# MultiSensor_MPL_PCA_0805.net
KiCad netlist of a schematic drawn in EAGLE
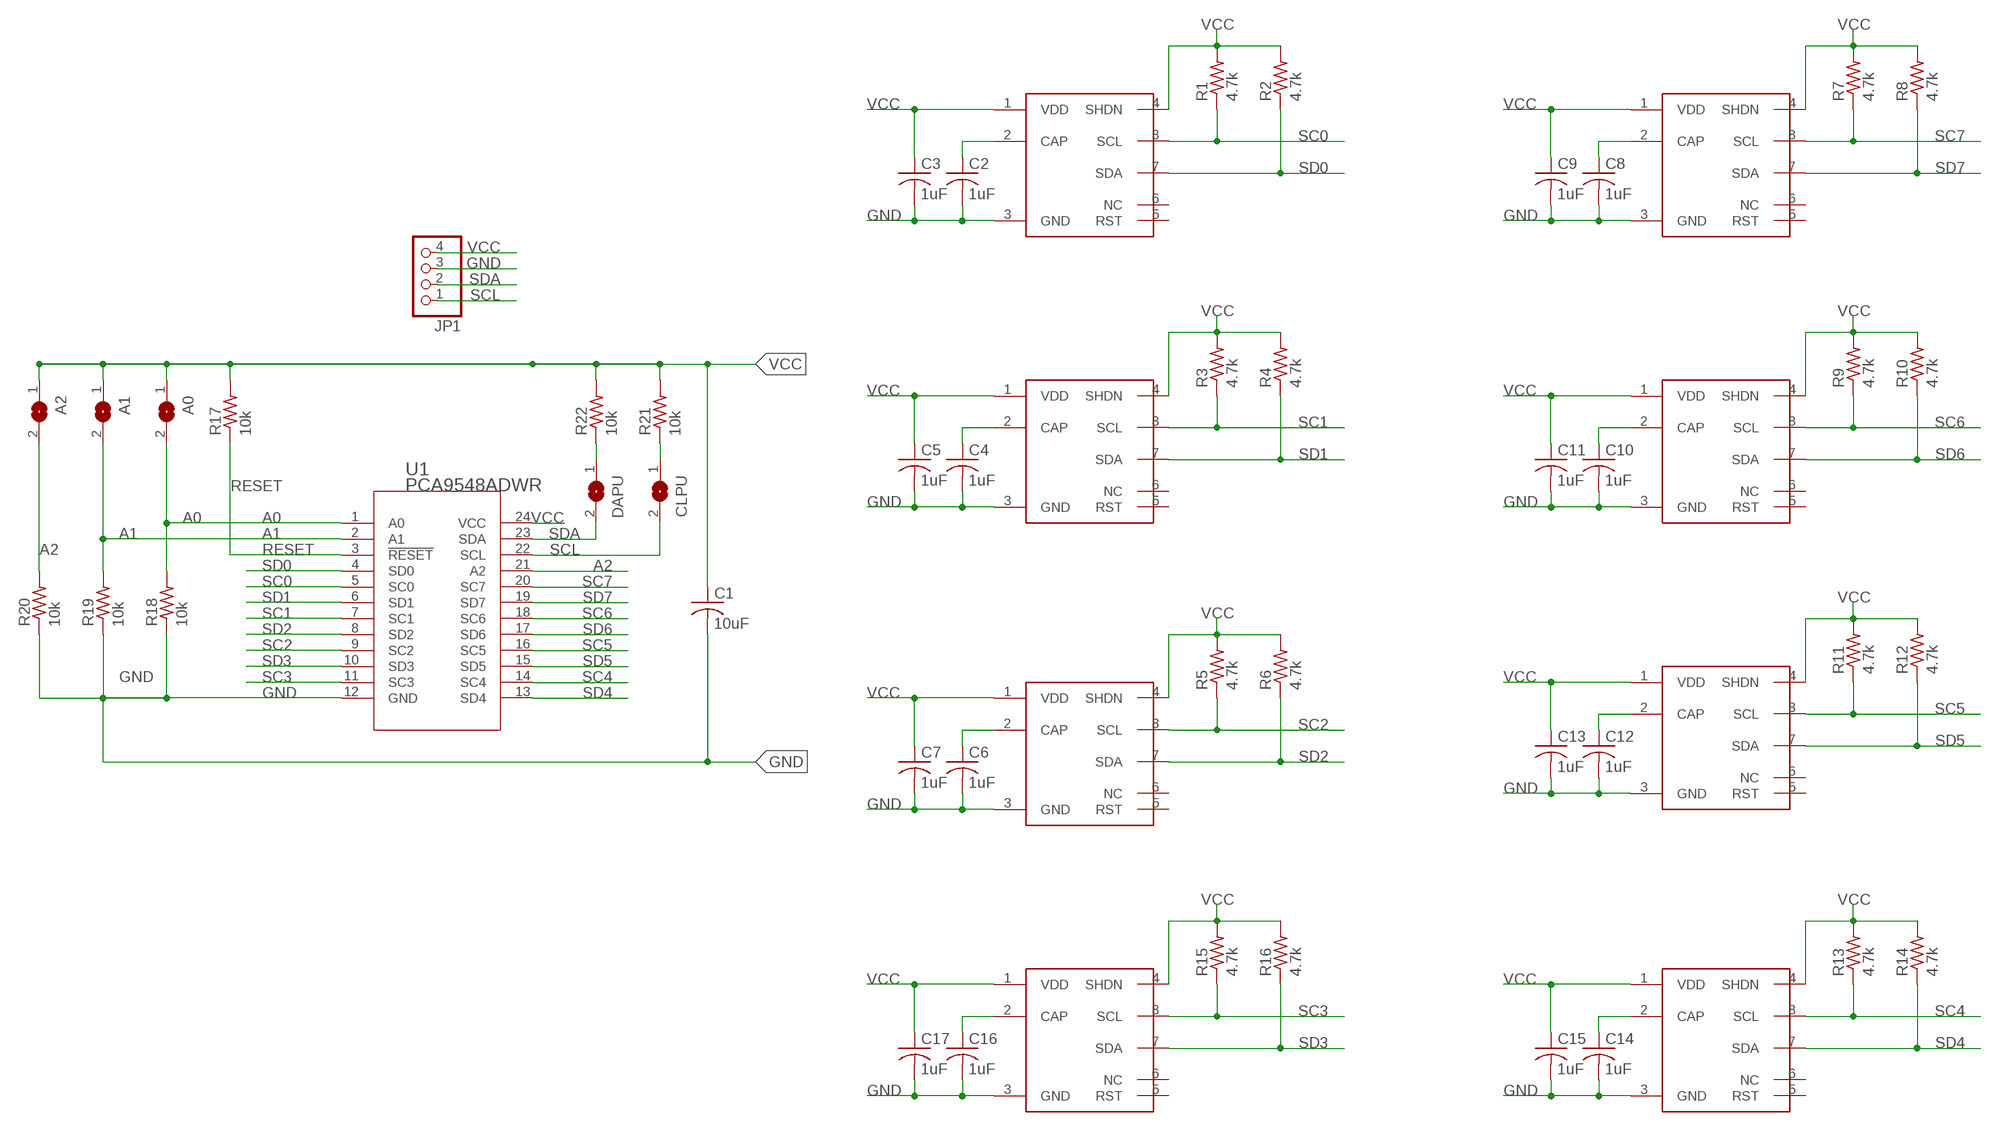
[diagram p0: schematic, sheet 1]

(export (version "E")
  (design (tool "Eeschema 10.0.6"))
  (components
    (comp (ref "A0") (value "SJ") (footprint "eagle-import:SJ") (libsource (lib "eagle-import") (part "SJ")))
    (comp (ref "A1") (value "SJ") (footprint "eagle-import:SJ") (libsource (lib "eagle-import") (part "SJ")))
    (comp (ref "A2") (value "SJ") (footprint "eagle-import:SJ") (libsource (lib "eagle-import") (part "SJ")))
    (comp (ref "B1")
      (value "MPL115A2T1")
      (footprint "eagle-import:MPL115A2T1")
      (libsource (lib "eagle-import") (part "MPL115A2T1"))
    )
    (comp (ref "B2")
      (value "MPL115A2T1")
      (footprint "eagle-import:MPL115A2T1")
      (libsource (lib "eagle-import") (part "MPL115A2T1"))
    )
    (comp (ref "B3")
      (value "MPL115A2T1")
      (footprint "eagle-import:MPL115A2T1")
      (libsource (lib "eagle-import") (part "MPL115A2T1"))
    )
    (comp (ref "B4")
      (value "MPL115A2T1")
      (footprint "eagle-import:MPL115A2T1")
      (libsource (lib "eagle-import") (part "MPL115A2T1"))
    )
    (comp (ref "B5")
      (value "MPL115A2T1")
      (footprint "eagle-import:MPL115A2T1")
      (libsource (lib "eagle-import") (part "MPL115A2T1"))
    )
    (comp (ref "B6")
      (value "MPL115A2T1")
      (footprint "eagle-import:MPL115A2T1")
      (libsource (lib "eagle-import") (part "MPL115A2T1"))
    )
    (comp (ref "B7")
      (value "MPL115A2T1")
      (footprint "eagle-import:MPL115A2T1")
      (libsource (lib "eagle-import") (part "MPL115A2T1"))
    )
    (comp (ref "B8")
      (value "MPL115A2T1")
      (footprint "eagle-import:MPL115A2T1")
      (libsource (lib "eagle-import") (part "MPL115A2T1"))
    )
    (comp (ref "C1")
      (value "10uF")
      (footprint "eagle-import:C1206")
      (libsource (lib "eagle-import") (part "C-USC1206"))
    )
    (comp (ref "C2")
      (value "1uF")
      (footprint "eagle-import:C0805")
      (libsource (lib "eagle-import") (part "C-USC0805"))
    )
    (comp (ref "C3")
      (value "1uF")
      (footprint "eagle-import:C0805")
      (libsource (lib "eagle-import") (part "C-USC0805"))
    )
    (comp (ref "C4")
      (value "1uF")
      (footprint "eagle-import:C0805")
      (libsource (lib "eagle-import") (part "C-USC0805"))
    )
    (comp (ref "C5")
      (value "1uF")
      (footprint "eagle-import:C0805")
      (libsource (lib "eagle-import") (part "C-USC0805"))
    )
    (comp (ref "C6")
      (value "1uF")
      (footprint "eagle-import:C0805")
      (libsource (lib "eagle-import") (part "C-USC0805"))
    )
    (comp (ref "C7")
      (value "1uF")
      (footprint "eagle-import:C0805")
      (libsource (lib "eagle-import") (part "C-USC0805"))
    )
    (comp (ref "C8")
      (value "1uF")
      (footprint "eagle-import:C0805")
      (libsource (lib "eagle-import") (part "C-USC0805"))
    )
    (comp (ref "C9")
      (value "1uF")
      (footprint "eagle-import:C0805")
      (libsource (lib "eagle-import") (part "C-USC0805"))
    )
    (comp (ref "C10")
      (value "1uF")
      (footprint "eagle-import:C0805")
      (libsource (lib "eagle-import") (part "C-USC0805"))
    )
    (comp (ref "C11")
      (value "1uF")
      (footprint "eagle-import:C0805")
      (libsource (lib "eagle-import") (part "C-USC0805"))
    )
    (comp (ref "C12")
      (value "1uF")
      (footprint "eagle-import:C0805")
      (libsource (lib "eagle-import") (part "C-USC0805"))
    )
    (comp (ref "C13")
      (value "1uF")
      (footprint "eagle-import:C0805")
      (libsource (lib "eagle-import") (part "C-USC0805"))
    )
    (comp (ref "C14")
      (value "1uF")
      (footprint "eagle-import:C0805")
      (libsource (lib "eagle-import") (part "C-USC0805"))
    )
    (comp (ref "C15")
      (value "1uF")
      (footprint "eagle-import:C0805")
      (libsource (lib "eagle-import") (part "C-USC0805"))
    )
    (comp (ref "C16")
      (value "1uF")
      (footprint "eagle-import:C0805")
      (libsource (lib "eagle-import") (part "C-USC0805"))
    )
    (comp (ref "C17")
      (value "1uF")
      (footprint "eagle-import:C0805")
      (libsource (lib "eagle-import") (part "C-USC0805"))
    )
    (comp (ref "CLPU")
      (value "SJ")
      (footprint "eagle-import:SJ")
      (libsource (lib "eagle-import") (part "SJ"))
    )
    (comp (ref "DAPU")
      (value "SJ")
      (footprint "eagle-import:SJ")
      (libsource (lib "eagle-import") (part "SJ"))
    )
    (comp (ref "JP1")
      (value "PINHD-1X4")
      (footprint "eagle-import:1X04")
      (libsource (lib "eagle-import") (part "PINHD-1X4"))
    )
    (comp (ref "R1")
      (value "4.7k")
      (footprint "eagle-import:R0805")
      (libsource (lib "eagle-import") (part "R-US_R0805"))
    )
    (comp (ref "R2")
      (value "4.7k")
      (footprint "eagle-import:R0805")
      (libsource (lib "eagle-import") (part "R-US_R0805"))
    )
    (comp (ref "R3")
      (value "4.7k")
      (footprint "eagle-import:R0805")
      (libsource (lib "eagle-import") (part "R-US_R0805"))
    )
    (comp (ref "R4")
      (value "4.7k")
      (footprint "eagle-import:R0805")
      (libsource (lib "eagle-import") (part "R-US_R0805"))
    )
    (comp (ref "R5")
      (value "4.7k")
      (footprint "eagle-import:R0805")
      (libsource (lib "eagle-import") (part "R-US_R0805"))
    )
    (comp (ref "R6")
      (value "4.7k")
      (footprint "eagle-import:R0805")
      (libsource (lib "eagle-import") (part "R-US_R0805"))
    )
    (comp (ref "R7")
      (value "4.7k")
      (footprint "eagle-import:R0805")
      (libsource (lib "eagle-import") (part "R-US_R0805"))
    )
    (comp (ref "R8")
      (value "4.7k")
      (footprint "eagle-import:R0805")
      (libsource (lib "eagle-import") (part "R-US_R0805"))
    )
    (comp (ref "R9")
      (value "4.7k")
      (footprint "eagle-import:R0805")
      (libsource (lib "eagle-import") (part "R-US_R0805"))
    )
    (comp (ref "R10")
      (value "4.7k")
      (footprint "eagle-import:R0805")
      (libsource (lib "eagle-import") (part "R-US_R0805"))
    )
    (comp (ref "R11")
      (value "4.7k")
      (footprint "eagle-import:R0805")
      (libsource (lib "eagle-import") (part "R-US_R0805"))
    )
    (comp (ref "R12")
      (value "4.7k")
      (footprint "eagle-import:R0805")
      (libsource (lib "eagle-import") (part "R-US_R0805"))
    )
    (comp (ref "R13")
      (value "4.7k")
      (footprint "eagle-import:R0805")
      (libsource (lib "eagle-import") (part "R-US_R0805"))
    )
    (comp (ref "R14")
      (value "4.7k")
      (footprint "eagle-import:R0805")
      (libsource (lib "eagle-import") (part "R-US_R0805"))
    )
    (comp (ref "R15")
      (value "4.7k")
      (footprint "eagle-import:R0805")
      (libsource (lib "eagle-import") (part "R-US_R0805"))
    )
    (comp (ref "R16")
      (value "4.7k")
      (footprint "eagle-import:R0805")
      (libsource (lib "eagle-import") (part "R-US_R0805"))
    )
    (comp (ref "R17")
      (value "10k")
      (footprint "eagle-import:R0805")
      (libsource (lib "eagle-import") (part "resistor_348_R-US_R0805"))
    )
    (comp (ref "R18")
      (value "10k")
      (footprint "eagle-import:R0805")
      (libsource (lib "eagle-import") (part "resistor_348_R-US_R0805"))
    )
    (comp (ref "R19")
      (value "10k")
      (footprint "eagle-import:R0805")
      (libsource (lib "eagle-import") (part "resistor_348_R-US_R0805"))
    )
    (comp (ref "R20")
      (value "10k")
      (footprint "eagle-import:R0805")
      (libsource (lib "eagle-import") (part "resistor_348_R-US_R0805"))
    )
    (comp (ref "R21")
      (value "10k")
      (footprint "eagle-import:R0805")
      (libsource (lib "eagle-import") (part "resistor_348_R-US_R0805"))
    )
    (comp (ref "R22")
      (value "10k")
      (footprint "eagle-import:R0805")
      (libsource (lib "eagle-import") (part "resistor_348_R-US_R0805"))
    )
    (comp (ref "U1")
      (value "PCA9548ADWR")
      (footprint "eagle-import:DW24")
      (fields
        (field (name "GENERIC_PART_NUMBER") "PCA9548A")
        (field (name "MANUFACTURER") "Texas Instruments")
      )
      (libsource (lib "eagle-import") (part "PCA9548ADWR"))
    )
  )
  (nets
    (net (code "1") (name "/A0") (class "Default")
      (node (ref "A0") (pin "2") (pinfunction "2_2") (pintype "passive"))
      (node (ref "R18") (pin "2") (pinfunction "2_2") (pintype "passive"))
      (node (ref "U1") (pin "1") (pinfunction "A0_1") (pintype "input"))
    )
    (net (code "2") (name "/A1") (class "Default")
      (node (ref "A1") (pin "2") (pinfunction "2_2") (pintype "passive"))
      (node (ref "R19") (pin "2") (pinfunction "2_2") (pintype "passive"))
      (node (ref "U1") (pin "2") (pinfunction "A1_2") (pintype "input"))
    )
    (net (code "3") (name "/A2") (class "Default")
      (node (ref "A2") (pin "2") (pinfunction "2_2") (pintype "passive"))
      (node (ref "R20") (pin "2") (pinfunction "2_2") (pintype "passive"))
      (node (ref "U1") (pin "21") (pinfunction "A2_21") (pintype "input"))
    )
    (net (code "4") (name "/RESET") (class "Default")
      (node (ref "R17") (pin "1") (pinfunction "1_1") (pintype "passive"))
      (node (ref "U1") (pin "3") (pinfunction "~{RESET}_3") (pintype "input"))
    )
    (net (code "5") (name "/SC0") (class "Default")
      (node (ref "B1") (pin "8") (pinfunction "SCL_8") (pintype "bidirectional"))
      (node (ref "R1") (pin "1") (pinfunction "1_1") (pintype "passive"))
      (node (ref "U1") (pin "5") (pinfunction "SC0_5") (pintype "passive"))
    )
    (net (code "6") (name "/SC1") (class "Default")
      (node (ref "B2") (pin "8") (pinfunction "SCL_8") (pintype "bidirectional"))
      (node (ref "R3") (pin "1") (pinfunction "1_1") (pintype "passive"))
      (node (ref "U1") (pin "7") (pinfunction "SC1_7") (pintype "passive"))
    )
    (net (code "7") (name "/SC2") (class "Default")
      (node (ref "B3") (pin "8") (pinfunction "SCL_8") (pintype "bidirectional"))
      (node (ref "R5") (pin "1") (pinfunction "1_1") (pintype "passive"))
      (node (ref "U1") (pin "9") (pinfunction "SC2_9") (pintype "passive"))
    )
    (net (code "8") (name "/SC3") (class "Default")
      (node (ref "B8") (pin "8") (pinfunction "SCL_8") (pintype "bidirectional"))
      (node (ref "R15") (pin "1") (pinfunction "1_1") (pintype "passive"))
      (node (ref "U1") (pin "11") (pinfunction "SC3_11") (pintype "passive"))
    )
    (net (code "9") (name "/SC4") (class "Default")
      (node (ref "B7") (pin "8") (pinfunction "SCL_8") (pintype "bidirectional"))
      (node (ref "R13") (pin "1") (pinfunction "1_1") (pintype "passive"))
      (node (ref "U1") (pin "14") (pinfunction "SC4_14") (pintype "passive"))
    )
    (net (code "10") (name "/SC5") (class "Default")
      (node (ref "B6") (pin "8") (pinfunction "SCL_8") (pintype "bidirectional"))
      (node (ref "R11") (pin "1") (pinfunction "1_1") (pintype "passive"))
      (node (ref "U1") (pin "16") (pinfunction "SC5_16") (pintype "passive"))
    )
    (net (code "11") (name "/SC6") (class "Default")
      (node (ref "B5") (pin "8") (pinfunction "SCL_8") (pintype "bidirectional"))
      (node (ref "R9") (pin "1") (pinfunction "1_1") (pintype "passive"))
      (node (ref "U1") (pin "18") (pinfunction "SC6_18") (pintype "passive"))
    )
    (net (code "12") (name "/SC7") (class "Default")
      (node (ref "B4") (pin "8") (pinfunction "SCL_8") (pintype "bidirectional"))
      (node (ref "R7") (pin "1") (pinfunction "1_1") (pintype "passive"))
      (node (ref "U1") (pin "20") (pinfunction "SC7_20") (pintype "passive"))
    )
    (net (code "13") (name "/SCL") (class "Default")
      (node (ref "CLPU") (pin "2") (pinfunction "2_2") (pintype "passive"))
      (node (ref "JP1") (pin "1") (pinfunction "1_1") (pintype "passive"))
      (node (ref "U1") (pin "22") (pinfunction "SCL_22") (pintype "passive"))
    )
    (net (code "14") (name "/SD0") (class "Default")
      (node (ref "B1") (pin "7") (pinfunction "SDA_7") (pintype "bidirectional"))
      (node (ref "R2") (pin "1") (pinfunction "1_1") (pintype "passive"))
      (node (ref "U1") (pin "4") (pinfunction "SD0_4") (pintype "passive"))
    )
    (net (code "15") (name "/SD1") (class "Default")
      (node (ref "B2") (pin "7") (pinfunction "SDA_7") (pintype "bidirectional"))
      (node (ref "R4") (pin "1") (pinfunction "1_1") (pintype "passive"))
      (node (ref "U1") (pin "6") (pinfunction "SD1_6") (pintype "passive"))
    )
    (net (code "16") (name "/SD2") (class "Default")
      (node (ref "B3") (pin "7") (pinfunction "SDA_7") (pintype "bidirectional"))
      (node (ref "R6") (pin "1") (pinfunction "1_1") (pintype "passive"))
      (node (ref "U1") (pin "8") (pinfunction "SD2_8") (pintype "passive"))
    )
    (net (code "17") (name "/SD3") (class "Default")
      (node (ref "B8") (pin "7") (pinfunction "SDA_7") (pintype "bidirectional"))
      (node (ref "R16") (pin "1") (pinfunction "1_1") (pintype "passive"))
      (node (ref "U1") (pin "10") (pinfunction "SD3_10") (pintype "passive"))
    )
    (net (code "18") (name "/SD4") (class "Default")
      (node (ref "B7") (pin "7") (pinfunction "SDA_7") (pintype "bidirectional"))
      (node (ref "R14") (pin "1") (pinfunction "1_1") (pintype "passive"))
      (node (ref "U1") (pin "13") (pinfunction "SD4_13") (pintype "passive"))
    )
    (net (code "19") (name "/SD5") (class "Default")
      (node (ref "B6") (pin "7") (pinfunction "SDA_7") (pintype "bidirectional"))
      (node (ref "R12") (pin "1") (pinfunction "1_1") (pintype "passive"))
      (node (ref "U1") (pin "15") (pinfunction "SD5_15") (pintype "passive"))
    )
    (net (code "20") (name "/SD6") (class "Default")
      (node (ref "B5") (pin "7") (pinfunction "SDA_7") (pintype "bidirectional"))
      (node (ref "R10") (pin "1") (pinfunction "1_1") (pintype "passive"))
      (node (ref "U1") (pin "17") (pinfunction "SD6_17") (pintype "passive"))
    )
    (net (code "21") (name "/SD7") (class "Default")
      (node (ref "B4") (pin "7") (pinfunction "SDA_7") (pintype "bidirectional"))
      (node (ref "R8") (pin "1") (pinfunction "1_1") (pintype "passive"))
      (node (ref "U1") (pin "19") (pinfunction "SD7_19") (pintype "passive"))
    )
    (net (code "22") (name "/SDA") (class "Default")
      (node (ref "DAPU") (pin "2") (pinfunction "2_2") (pintype "passive"))
      (node (ref "JP1") (pin "2") (pinfunction "2_2") (pintype "passive"))
      (node (ref "U1") (pin "23") (pinfunction "SDA_23") (pintype "passive"))
    )
    (net (code "23") (name "GND") (class "Default")
      (node (ref "B1") (pin "3") (pinfunction "GND_3") (pintype "bidirectional"))
      (node (ref "B2") (pin "3") (pinfunction "GND_3") (pintype "bidirectional"))
      (node (ref "B3") (pin "3") (pinfunction "GND_3") (pintype "bidirectional"))
      (node (ref "B4") (pin "3") (pinfunction "GND_3") (pintype "bidirectional"))
      (node (ref "B5") (pin "3") (pinfunction "GND_3") (pintype "bidirectional"))
      (node (ref "B6") (pin "3") (pinfunction "GND_3") (pintype "bidirectional"))
      (node (ref "B7") (pin "3") (pinfunction "GND_3") (pintype "bidirectional"))
      (node (ref "B8") (pin "3") (pinfunction "GND_3") (pintype "bidirectional"))
      (node (ref "C1") (pin "2") (pinfunction "2_2") (pintype "passive"))
      (node (ref "C10") (pin "2") (pinfunction "2_2") (pintype "passive"))
      (node (ref "C11") (pin "2") (pinfunction "2_2") (pintype "passive"))
      (node (ref "C12") (pin "2") (pinfunction "2_2") (pintype "passive"))
      (node (ref "C13") (pin "2") (pinfunction "2_2") (pintype "passive"))
      (node (ref "C14") (pin "2") (pinfunction "2_2") (pintype "passive"))
      (node (ref "C15") (pin "2") (pinfunction "2_2") (pintype "passive"))
      (node (ref "C16") (pin "2") (pinfunction "2_2") (pintype "passive"))
      (node (ref "C17") (pin "2") (pinfunction "2_2") (pintype "passive"))
      (node (ref "C2") (pin "2") (pinfunction "2_2") (pintype "passive"))
      (node (ref "C3") (pin "2") (pinfunction "2_2") (pintype "passive"))
      (node (ref "C4") (pin "2") (pinfunction "2_2") (pintype "passive"))
      (node (ref "C5") (pin "2") (pinfunction "2_2") (pintype "passive"))
      (node (ref "C6") (pin "2") (pinfunction "2_2") (pintype "passive"))
      (node (ref "C7") (pin "2") (pinfunction "2_2") (pintype "passive"))
      (node (ref "C8") (pin "2") (pinfunction "2_2") (pintype "passive"))
      (node (ref "C9") (pin "2") (pinfunction "2_2") (pintype "passive"))
      (node (ref "JP1") (pin "3") (pinfunction "3_3") (pintype "passive"))
      (node (ref "R18") (pin "1") (pinfunction "1_1") (pintype "passive"))
      (node (ref "R19") (pin "1") (pinfunction "1_1") (pintype "passive"))
      (node (ref "R20") (pin "1") (pinfunction "1_1") (pintype "passive"))
      (node (ref "U1") (pin "12") (pinfunction "GND_12") (pintype "power_in"))
    )
    (net (code "24") (name "Net-(B1-CAP)") (class "Default")
      (node (ref "B1") (pin "2") (pinfunction "CAP_2") (pintype "bidirectional"))
      (node (ref "C2") (pin "1") (pinfunction "1_1") (pintype "passive"))
    )
    (net (code "25") (name "Net-(B2-CAP)") (class "Default")
      (node (ref "B2") (pin "2") (pinfunction "CAP_2") (pintype "bidirectional"))
      (node (ref "C4") (pin "1") (pinfunction "1_1") (pintype "passive"))
    )
    (net (code "26") (name "Net-(B3-CAP)") (class "Default")
      (node (ref "B3") (pin "2") (pinfunction "CAP_2") (pintype "bidirectional"))
      (node (ref "C6") (pin "1") (pinfunction "1_1") (pintype "passive"))
    )
    (net (code "27") (name "Net-(B4-CAP)") (class "Default")
      (node (ref "B4") (pin "2") (pinfunction "CAP_2") (pintype "bidirectional"))
      (node (ref "C8") (pin "1") (pinfunction "1_1") (pintype "passive"))
    )
    (net (code "28") (name "Net-(B5-CAP)") (class "Default")
      (node (ref "B5") (pin "2") (pinfunction "CAP_2") (pintype "bidirectional"))
      (node (ref "C10") (pin "1") (pinfunction "1_1") (pintype "passive"))
    )
    (net (code "29") (name "Net-(B6-CAP)") (class "Default")
      (node (ref "B6") (pin "2") (pinfunction "CAP_2") (pintype "bidirectional"))
      (node (ref "C12") (pin "1") (pinfunction "1_1") (pintype "passive"))
    )
    (net (code "30") (name "Net-(B7-CAP)") (class "Default")
      (node (ref "B7") (pin "2") (pinfunction "CAP_2") (pintype "bidirectional"))
      (node (ref "C14") (pin "1") (pinfunction "1_1") (pintype "passive"))
    )
    (net (code "31") (name "Net-(B8-CAP)") (class "Default")
      (node (ref "B8") (pin "2") (pinfunction "CAP_2") (pintype "bidirectional"))
      (node (ref "C16") (pin "1") (pinfunction "1_1") (pintype "passive"))
    )
    (net (code "32") (name "Net-(CLPU-Pad1)") (class "Default")
      (node (ref "CLPU") (pin "1") (pinfunction "1_1") (pintype "passive"))
      (node (ref "R21") (pin "1") (pinfunction "1_1") (pintype "passive"))
    )
    (net (code "33") (name "Net-(DAPU-Pad1)") (class "Default")
      (node (ref "DAPU") (pin "1") (pinfunction "1_1") (pintype "passive"))
      (node (ref "R22") (pin "1") (pinfunction "1_1") (pintype "passive"))
    )
    (net (code "34") (name "VCC") (class "Default")
      (node (ref "A0") (pin "1") (pinfunction "1_1") (pintype "passive"))
      (node (ref "A1") (pin "1") (pinfunction "1_1") (pintype "passive"))
      (node (ref "A2") (pin "1") (pinfunction "1_1") (pintype "passive"))
      (node (ref "B1") (pin "1") (pinfunction "VDD_1") (pintype "bidirectional"))
      (node (ref "B1") (pin "4") (pinfunction "SHDN_4") (pintype "bidirectional"))
      (node (ref "B2") (pin "1") (pinfunction "VDD_1") (pintype "bidirectional"))
      (node (ref "B2") (pin "4") (pinfunction "SHDN_4") (pintype "bidirectional"))
      (node (ref "B3") (pin "1") (pinfunction "VDD_1") (pintype "bidirectional"))
      (node (ref "B3") (pin "4") (pinfunction "SHDN_4") (pintype "bidirectional"))
      (node (ref "B4") (pin "1") (pinfunction "VDD_1") (pintype "bidirectional"))
      (node (ref "B4") (pin "4") (pinfunction "SHDN_4") (pintype "bidirectional"))
      (node (ref "B5") (pin "1") (pinfunction "VDD_1") (pintype "bidirectional"))
      (node (ref "B5") (pin "4") (pinfunction "SHDN_4") (pintype "bidirectional"))
      (node (ref "B6") (pin "1") (pinfunction "VDD_1") (pintype "bidirectional"))
      (node (ref "B6") (pin "4") (pinfunction "SHDN_4") (pintype "bidirectional"))
      (node (ref "B7") (pin "1") (pinfunction "VDD_1") (pintype "bidirectional"))
      (node (ref "B7") (pin "4") (pinfunction "SHDN_4") (pintype "bidirectional"))
      (node (ref "B8") (pin "1") (pinfunction "VDD_1") (pintype "bidirectional"))
      (node (ref "B8") (pin "4") (pinfunction "SHDN_4") (pintype "bidirectional"))
      (node (ref "C1") (pin "1") (pinfunction "1_1") (pintype "passive"))
      (node (ref "C11") (pin "1") (pinfunction "1_1") (pintype "passive"))
      (node (ref "C13") (pin "1") (pinfunction "1_1") (pintype "passive"))
      (node (ref "C15") (pin "1") (pinfunction "1_1") (pintype "passive"))
      (node (ref "C17") (pin "1") (pinfunction "1_1") (pintype "passive"))
      (node (ref "C3") (pin "1") (pinfunction "1_1") (pintype "passive"))
      (node (ref "C5") (pin "1") (pinfunction "1_1") (pintype "passive"))
      (node (ref "C7") (pin "1") (pinfunction "1_1") (pintype "passive"))
      (node (ref "C9") (pin "1") (pinfunction "1_1") (pintype "passive"))
      (node (ref "JP1") (pin "4") (pinfunction "4_4") (pintype "passive"))
      (node (ref "R1") (pin "2") (pinfunction "2_2") (pintype "passive"))
      (node (ref "R10") (pin "2") (pinfunction "2_2") (pintype "passive"))
      (node (ref "R11") (pin "2") (pinfunction "2_2") (pintype "passive"))
      (node (ref "R12") (pin "2") (pinfunction "2_2") (pintype "passive"))
      (node (ref "R13") (pin "2") (pinfunction "2_2") (pintype "passive"))
      (node (ref "R14") (pin "2") (pinfunction "2_2") (pintype "passive"))
      (node (ref "R15") (pin "2") (pinfunction "2_2") (pintype "passive"))
      (node (ref "R16") (pin "2") (pinfunction "2_2") (pintype "passive"))
      (node (ref "R17") (pin "2") (pinfunction "2_2") (pintype "passive"))
      (node (ref "R2") (pin "2") (pinfunction "2_2") (pintype "passive"))
      (node (ref "R21") (pin "2") (pinfunction "2_2") (pintype "passive"))
      (node (ref "R22") (pin "2") (pinfunction "2_2") (pintype "passive"))
      (node (ref "R3") (pin "2") (pinfunction "2_2") (pintype "passive"))
      (node (ref "R4") (pin "2") (pinfunction "2_2") (pintype "passive"))
      (node (ref "R5") (pin "2") (pinfunction "2_2") (pintype "passive"))
      (node (ref "R6") (pin "2") (pinfunction "2_2") (pintype "passive"))
      (node (ref "R7") (pin "2") (pinfunction "2_2") (pintype "passive"))
      (node (ref "R8") (pin "2") (pinfunction "2_2") (pintype "passive"))
      (node (ref "R9") (pin "2") (pinfunction "2_2") (pintype "passive"))
      (node (ref "U1") (pin "24") (pinfunction "VCC_24") (pintype "power_in"))
    )
    (net (code "35") (name "unconnected-(B1-NC-Pad6)") (class "Default")
      (node (ref "B1") (pin "6") (pinfunction "NC_6") (pintype "bidirectional"))
    )
    (net (code "36") (name "unconnected-(B1-RST-Pad5)") (class "Default")
      (node (ref "B1") (pin "5") (pinfunction "RST_5") (pintype "bidirectional"))
    )
    (net (code "37") (name "unconnected-(B2-NC-Pad6)") (class "Default")
      (node (ref "B2") (pin "6") (pinfunction "NC_6") (pintype "bidirectional"))
    )
    (net (code "38") (name "unconnected-(B2-RST-Pad5)") (class "Default")
      (node (ref "B2") (pin "5") (pinfunction "RST_5") (pintype "bidirectional"))
    )
    (net (code "39") (name "unconnected-(B3-NC-Pad6)") (class "Default")
      (node (ref "B3") (pin "6") (pinfunction "NC_6") (pintype "bidirectional"))
    )
    (net (code "40") (name "unconnected-(B3-RST-Pad5)") (class "Default")
      (node (ref "B3") (pin "5") (pinfunction "RST_5") (pintype "bidirectional"))
    )
    (net (code "41") (name "unconnected-(B4-NC-Pad6)") (class "Default")
      (node (ref "B4") (pin "6") (pinfunction "NC_6") (pintype "bidirectional"))
    )
    (net (code "42") (name "unconnected-(B4-RST-Pad5)") (class "Default")
      (node (ref "B4") (pin "5") (pinfunction "RST_5") (pintype "bidirectional"))
    )
    (net (code "43") (name "unconnected-(B5-NC-Pad6)") (class "Default")
      (node (ref "B5") (pin "6") (pinfunction "NC_6") (pintype "bidirectional"))
    )
    (net (code "44") (name "unconnected-(B5-RST-Pad5)") (class "Default")
      (node (ref "B5") (pin "5") (pinfunction "RST_5") (pintype "bidirectional"))
    )
    (net (code "45") (name "unconnected-(B6-NC-Pad6)") (class "Default")
      (node (ref "B6") (pin "6") (pinfunction "NC_6") (pintype "bidirectional"))
    )
    (net (code "46") (name "unconnected-(B6-RST-Pad5)") (class "Default")
      (node (ref "B6") (pin "5") (pinfunction "RST_5") (pintype "bidirectional"))
    )
    (net (code "47") (name "unconnected-(B7-NC-Pad6)") (class "Default")
      (node (ref "B7") (pin "6") (pinfunction "NC_6") (pintype "bidirectional"))
    )
    (net (code "48") (name "unconnected-(B7-RST-Pad5)") (class "Default")
      (node (ref "B7") (pin "5") (pinfunction "RST_5") (pintype "bidirectional"))
    )
    (net (code "49") (name "unconnected-(B8-NC-Pad6)") (class "Default")
      (node (ref "B8") (pin "6") (pinfunction "NC_6") (pintype "bidirectional"))
    )
    (net (code "50") (name "unconnected-(B8-RST-Pad5)") (class "Default")
      (node (ref "B8") (pin "5") (pinfunction "RST_5") (pintype "bidirectional"))
    )
  )
)
